# SCH_NFC-card_2024-10-18.net
KiCad netlist of a schematic drawn in EasyEDA
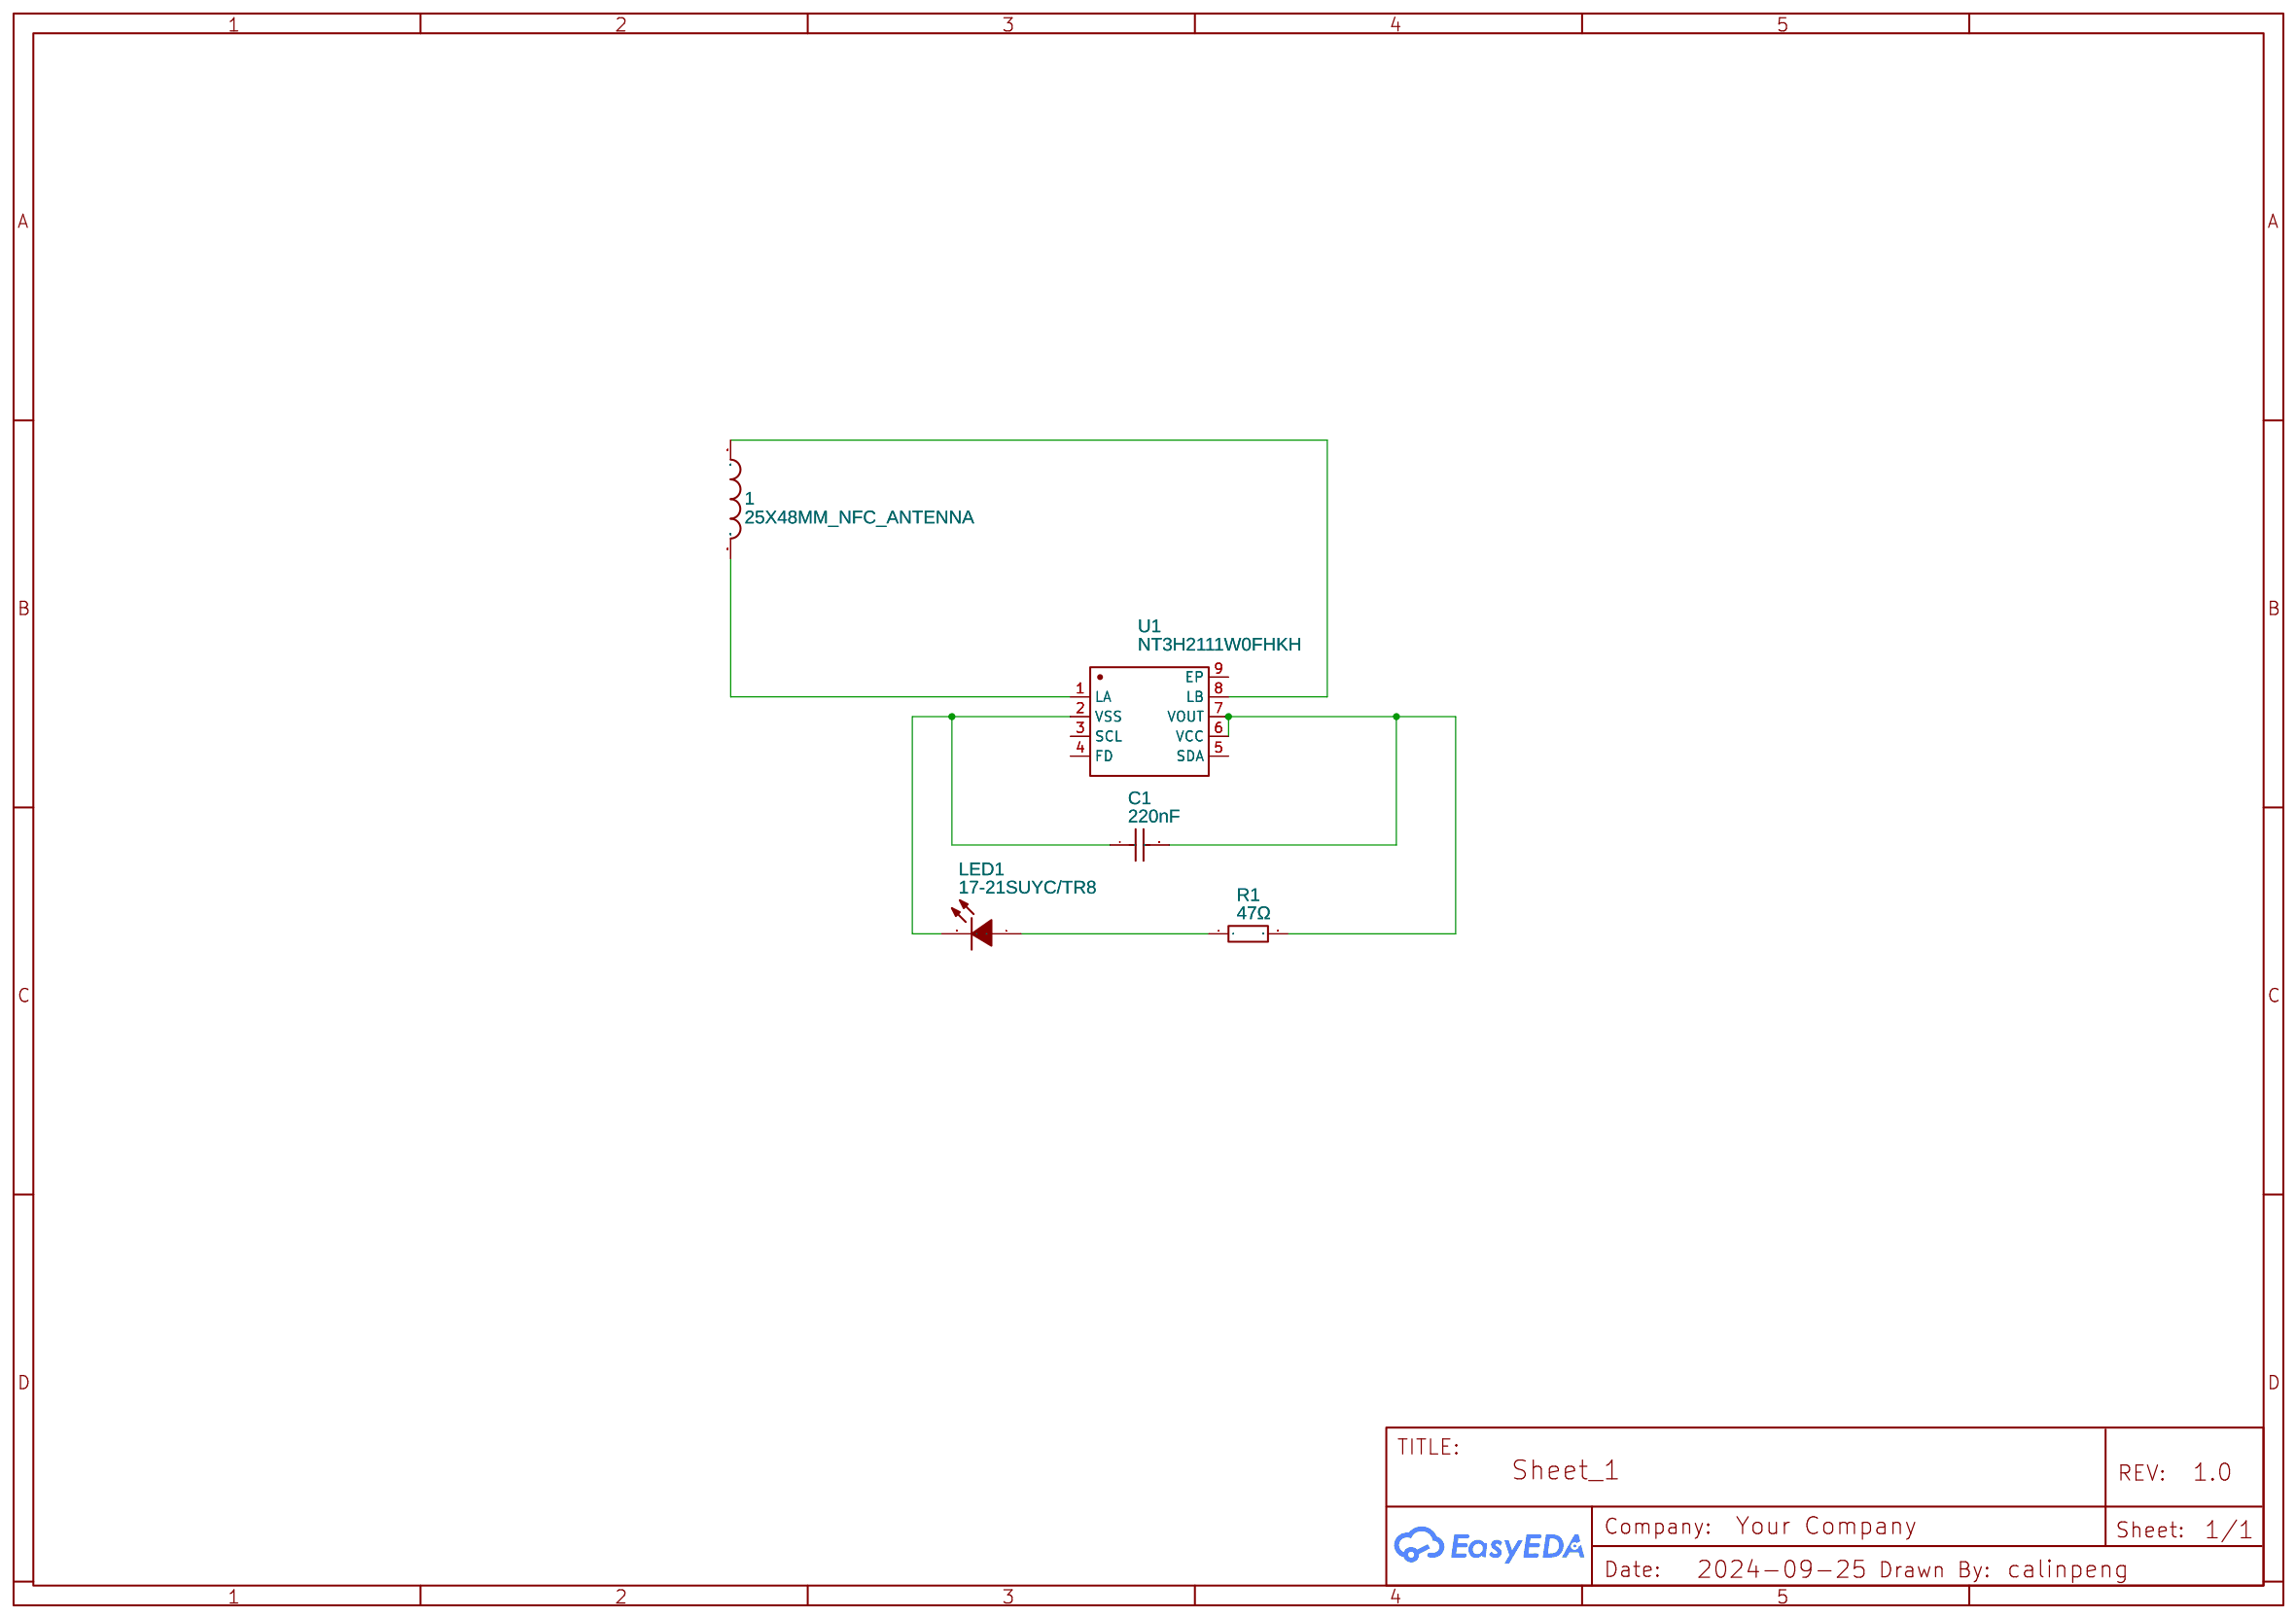
[diagram p0: schematic sheet]

(export (version "E")
  (design (tool "Eeschema 10.0.6"))
  (components
    (comp (ref "1") (value "25X48MM_NFC_ANTENNA") (libsource (lib "") (part "25X48MM_NFC_ANTENNA")))
    (comp (ref "C1")
      (value "220nF")
      (fields
        (field (name "Manufacturer Part") "CL10B224KA8NNNC")
        (field (name "Manufacturer") "SAMSUNG(三星)")
      )
      (libsource (lib "") (part "CL10B224KA8NNNC"))
    )
    (comp (ref "LED1")
      (value "17-21SUYC/TR8")
      (fields (field (name "Manufacturer Part") "KT-0805黄灯") (field (name "Manufacturer") "KENTO"))
      (libsource (lib "") (part "17-21SUYC/TR8"))
    )
    (comp (ref "R1")
      (value "47Ω")
      (fields
        (field (name "Manufacturer Part") "0603WAF470JT5E")
        (field (name "Manufacturer") "UNI-ROYAL(厚声)")
      )
      (libsource (lib "") (part "0603WAF470JT5E"))
    )
    (comp (ref "U1")
      (value "NT3H2111W0FHKH")
      (fields (field (name "Manufacturer") "NXP(恩智浦)"))
      (libsource (lib "") (part "NT3H2111W0FHKH"))
    )
  )
  (nets
    (net (code "1") (name "Net-(LED1-+)") (class "Default")
      (node (ref "LED1") (pin "1") (pinfunction "+_1") (pintype "unspecified"))
      (node (ref "R1") (pin "1") (pinfunction "1_1") (pintype "input"))
    )
    (net (code "2") (name "Net-(LED1--)") (class "Default")
      (node (ref "C1") (pin "1") (pinfunction "1_1") (pintype "input"))
      (node (ref "LED1") (pin "2") (pinfunction "-_2") (pintype "unspecified"))
      (node (ref "U1") (pin "2") (pinfunction "VSS_2") (pintype "unspecified"))
    )
    (net (code "3") (name "Net-(U1-LA)") (class "Default")
      (node (ref "1") (pin "P$2") (pinfunction "P$2_P$2") (pintype "bidirectional"))
      (node (ref "U1") (pin "1") (pinfunction "LA_1") (pintype "unspecified"))
    )
    (net (code "4") (name "Net-(U1-LB)") (class "Default")
      (node (ref "1") (pin "P$1") (pinfunction "P$1_P$1") (pintype "bidirectional"))
      (node (ref "U1") (pin "8") (pinfunction "LB_8") (pintype "unspecified"))
    )
    (net (code "5") (name "Net-(U1-VCC)") (class "Default")
      (node (ref "C1") (pin "2") (pinfunction "2_2") (pintype "input"))
      (node (ref "R1") (pin "2") (pinfunction "2_2") (pintype "input"))
      (node (ref "U1") (pin "6") (pinfunction "VCC_6") (pintype "unspecified"))
      (node (ref "U1") (pin "7") (pinfunction "VOUT_7") (pintype "unspecified"))
    )
    (net (code "6") (name "unconnected-(U1-EP-Pad9)") (class "Default")
      (node (ref "U1") (pin "9") (pinfunction "EP_9") (pintype "unspecified"))
    )
    (net (code "7") (name "unconnected-(U1-FD-Pad4)") (class "Default")
      (node (ref "U1") (pin "4") (pinfunction "FD_4") (pintype "unspecified"))
    )
    (net (code "8") (name "unconnected-(U1-SCL-Pad3)") (class "Default")
      (node (ref "U1") (pin "3") (pinfunction "SCL_3") (pintype "unspecified"))
    )
    (net (code "9") (name "unconnected-(U1-SDA-Pad5)") (class "Default")
      (node (ref "U1") (pin "5") (pinfunction "SDA_5") (pintype "unspecified"))
    )
  )
)
